# Power_Regulation.net
KiCad netlist of a schematic drawn in Altium Designer
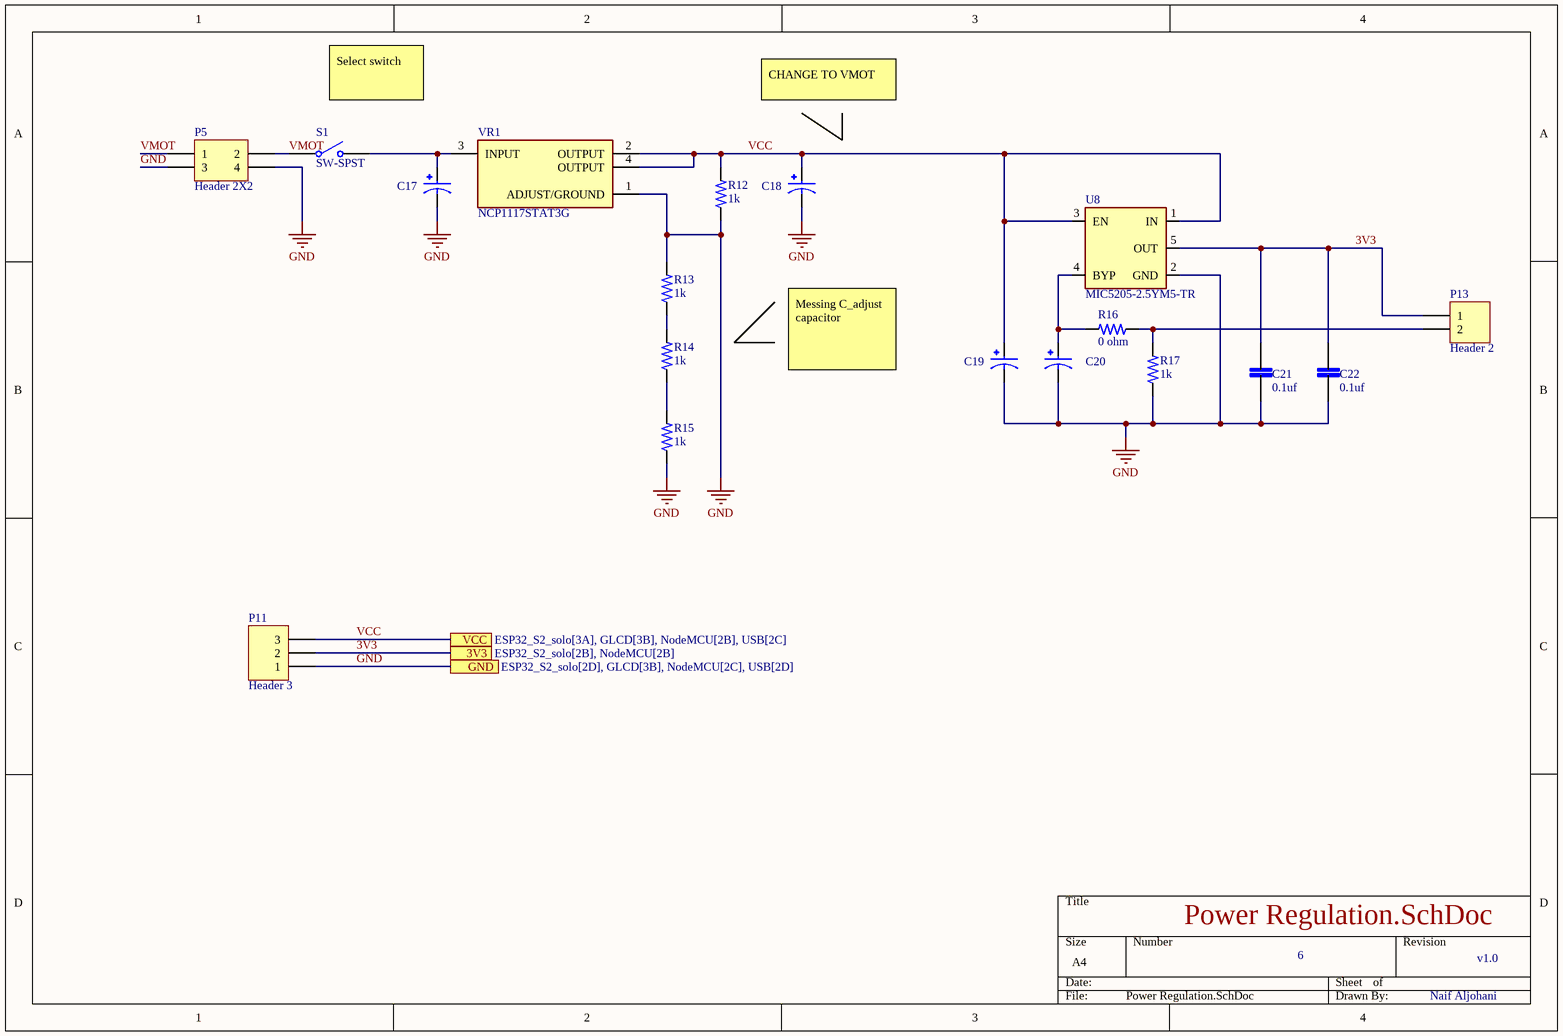
[diagram p0: Power Regulation.SchDoc]

(export (version "E")
  (design (tool "Eeschema 10.0.6"))
  (components
    (comp (ref "C17")
      (value "EEEHA1V101UP")
      (footprint "CAP_EEEHA1V101UP")
      (fields (field (name "MF") "{'manufacturer': u'Panasonic'}"))
      (libsource (lib "SnapEDA_Library") (part "EEEHA1V101UP"))
    )
    (comp (ref "C18")
      (value "EEEHA1V101UP")
      (footprint "CAP_EEEHA1V101UP")
      (fields (field (name "MF") "{'manufacturer': u'Panasonic'}"))
      (libsource (lib "SnapEDA_Library") (part "EEEHA1V101UP"))
    )
    (comp (ref "C19")
      (value "EEEHA1V101UP")
      (footprint "CAP_EEEHA1V101UP")
      (fields (field (name "MF") "{'manufacturer': u'Panasonic'}"))
      (libsource (lib "SnapEDA_Library") (part "EEEHA1V101UP"))
    )
    (comp (ref "C20")
      (value "EEEHA1V101UP")
      (footprint "CAP_EEEHA1V101UP")
      (fields (field (name "MF") "{'manufacturer': u'Panasonic'}"))
      (libsource (lib "SnapEDA_Library") (part "EEEHA1V101UP"))
    )
    (comp (ref "C21")
      (value "0.1uf")
      (footprint "CAPC2012X140N")
      (description "120PF 100V 10% 0805")
      (fields (field (name "MF") "{'manufacturer': u'AVX'}") (field (name "MP") "LD051A121KAB2A"))
      (libsource (lib "SnapEDA_Library") (part "LD051A121KAB2A"))
    )
    (comp (ref "C22")
      (value "0.1uf")
      (footprint "CAPC2012X140N")
      (description "120PF 100V 10% 0805")
      (fields (field (name "MF") "{'manufacturer': u'AVX'}") (field (name "MP") "LD051A121KAB2A"))
      (libsource (lib "SnapEDA_Library") (part "LD051A121KAB2A"))
    )
    (comp (ref "P5")
      (value "Header 2X2")
      (footprint "HDR2X2")
      (description "Header, 2-Pin, Dual row")
      (fields (field (name "PUBLISHER") "Altium Limited"))
      (libsource (lib "Miscellaneous Connectors") (part "Header 2X2"))
    )
    (comp (ref "P11")
      (value "Header 3")
      (footprint "HDR1X3")
      (description "Header, 3-Pin")
      (fields (field (name "PUBLISHER") "Altium Limited"))
      (libsource (lib "Miscellaneous Connectors") (part "Header 3"))
    )
    (comp (ref "P13")
      (value "Header 2")
      (footprint "HDR1X2")
      (description "Header, 2-Pin")
      (fields (field (name "PUBLISHER") "Altium Limited"))
      (libsource (lib "Miscellaneous Connectors") (part "Header 2"))
    )
    (comp (ref "R12")
      (value "1k")
      (footprint "RESC3115X65N")
      (description "RL73H 2B R43 1% 10 RL")
      (fields (field (name "MF") "{'manufacturer': u'TE Connectivity'}") (field (name "MP") "1-1879462-4"))
      (libsource (lib "SnapEDA_Library") (part "1-1879462-4"))
    )
    (comp (ref "R13")
      (value "1k")
      (footprint "RESC3115X65N")
      (description "RL73H 2B R43 1% 10 RL")
      (fields (field (name "MF") "{'manufacturer': u'TE Connectivity'}") (field (name "MP") "1-1879462-4"))
      (libsource (lib "SnapEDA_Library") (part "1-1879462-4"))
    )
    (comp (ref "R14")
      (value "1k")
      (footprint "RESC3115X65N")
      (description "RL73H 2B R43 1% 10 RL")
      (fields (field (name "MF") "{'manufacturer': u'TE Connectivity'}") (field (name "MP") "1-1879462-4"))
      (libsource (lib "SnapEDA_Library") (part "1-1879462-4"))
    )
    (comp (ref "R15")
      (value "1k")
      (footprint "RESC3115X65N")
      (description "RL73H 2B R43 1% 10 RL")
      (fields (field (name "MF") "{'manufacturer': u'TE Connectivity'}") (field (name "MP") "1-1879462-4"))
      (libsource (lib "SnapEDA_Library") (part "1-1879462-4"))
    )
    (comp (ref "R16")
      (value "0 ohm")
      (footprint "RESC3115X65N")
      (description "RL73H 2B R43 1% 10 RL")
      (fields (field (name "MF") "{'manufacturer': u'TE Connectivity'}") (field (name "MP") "1-1879462-4"))
      (libsource (lib "SnapEDA_Library") (part "1-1879462-4"))
    )
    (comp (ref "R17")
      (value "1k")
      (footprint "RESC3115X65N")
      (description "RL73H 2B R43 1% 10 RL")
      (fields (field (name "MF") "{'manufacturer': u'TE Connectivity'}") (field (name "MP") "1-1879462-4"))
      (libsource (lib "SnapEDA_Library") (part "1-1879462-4"))
    )
    (comp (ref "S1")
      (value "SW-SPST")
      (footprint "SPST-2")
      (description "Single-Pole, Single-Throw Switch")
      (fields (field (name "PUBLISHER") "Altium Limited"))
      (libsource (lib "Miscellaneous Devices") (part "SW-SPST"))
    )
    (comp (ref "U8")
      (value "MIC5205-2.5YM5-TR")
      (footprint "SOT95P280X145-5N")
      (description "MIC5205 Series 3 V Fixed Output 150 mA SMT Low-Noise LDO Regulator - SOT-23-5")
      (fields (field (name "MF") "{'manufacturer': u'Microchip Technology'}"))
      (libsource (lib "SnapEDA_Library") (part "MIC5205-2.5YM5-TR"))
    )
    (comp (ref "VR1")
      (value "NCP1117STAT3G")
      (footprint "VREG_NCP1117STAT3G")
      (description "Linear Voltage Regulator IC 1 Output 1A SOT-223")
      (fields (field (name "MF") "{'manufacturer': u'ON Semiconductor'}"))
      (libsource (lib "SnapEDA_Library") (part "NCP1117STAT3G"))
    )
  )
  (nets
    (net (code "1") (name "/3V3") (class "Default")
      (node (ref "C21") (pin "2") (pinfunction "2_2") (pintype "passive"))
      (node (ref "C22") (pin "2") (pinfunction "2_2") (pintype "passive"))
      (node (ref "P11") (pin "2") (pinfunction "2_2") (pintype "passive"))
      (node (ref "P13") (pin "1") (pinfunction "1_1") (pintype "passive"))
      (node (ref "U8") (pin "5") (pinfunction "OUT_5") (pintype "passive"))
    )
    (net (code "2") (name "/VCC") (class "Default")
      (node (ref "C18") (pin "1") (pinfunction "1_1") (pintype "passive"))
      (node (ref "C19") (pin "1") (pinfunction "1_1") (pintype "passive"))
      (node (ref "P11") (pin "3") (pinfunction "3_3") (pintype "passive"))
      (node (ref "R12") (pin "2") (pinfunction "2_2") (pintype "passive"))
      (node (ref "U8") (pin "1") (pinfunction "IN_1") (pintype "passive"))
      (node (ref "U8") (pin "3") (pinfunction "EN_3") (pintype "passive"))
      (node (ref "VR1") (pin "2") (pinfunction "OUTPUT_2") (pintype "passive"))
      (node (ref "VR1") (pin "4") (pinfunction "OUTPUT_4") (pintype "passive"))
    )
    (net (code "3") (name "/VMOT") (class "Default")
      (node (ref "P5") (pin "1") (pinfunction "1_1") (pintype "passive"))
      (node (ref "P5") (pin "2") (pinfunction "2_2") (pintype "passive"))
      (node (ref "S1") (pin "1") (pinfunction "COMMON_1") (pintype "passive"))
    )
    (net (code "4") (name "GND") (class "Default")
      (node (ref "C17") (pin "2") (pinfunction "2_2") (pintype "power_in"))
      (node (ref "C18") (pin "2") (pinfunction "2_2") (pintype "power_in"))
      (node (ref "C19") (pin "2") (pinfunction "2_2") (pintype "power_in"))
      (node (ref "C20") (pin "2") (pinfunction "2_2") (pintype "power_in"))
      (node (ref "C21") (pin "1") (pinfunction "1_1") (pintype "passive"))
      (node (ref "C22") (pin "1") (pinfunction "1_1") (pintype "passive"))
      (node (ref "P11") (pin "1") (pinfunction "1_1") (pintype "passive"))
      (node (ref "P5") (pin "3") (pinfunction "3_3") (pintype "passive"))
      (node (ref "P5") (pin "4") (pinfunction "4_4") (pintype "passive"))
      (node (ref "R12") (pin "1") (pinfunction "1_1") (pintype "passive"))
      (node (ref "R13") (pin "2") (pinfunction "2_2") (pintype "passive"))
      (node (ref "R15") (pin "1") (pinfunction "1_1") (pintype "passive"))
      (node (ref "R17") (pin "1") (pinfunction "1_1") (pintype "passive"))
      (node (ref "U8") (pin "2") (pinfunction "GND_2") (pintype "power_in"))
      (node (ref "VR1") (pin "1") (pinfunction "ADJUST/GROUND_1") (pintype "passive"))
    )
    (net (code "5") (name "Net-(P13-Pad2)") (class "Default")
      (node (ref "P13") (pin "2") (pinfunction "2_2") (pintype "passive"))
      (node (ref "R16") (pin "1") (pinfunction "1_1") (pintype "passive"))
      (node (ref "R17") (pin "2") (pinfunction "2_2") (pintype "passive"))
    )
    (net (code "6") (name "Net-(R13-Pad1)") (class "Default")
      (node (ref "R13") (pin "1") (pinfunction "1_1") (pintype "passive"))
      (node (ref "R14") (pin "2") (pinfunction "2_2") (pintype "passive"))
    )
    (net (code "7") (name "Net-(R14-Pad1)") (class "Default")
      (node (ref "R14") (pin "1") (pinfunction "1_1") (pintype "passive"))
      (node (ref "R15") (pin "2") (pinfunction "2_2") (pintype "passive"))
    )
    (net (code "8") (name "Net-(S1-NO)") (class "Default")
      (node (ref "C17") (pin "1") (pinfunction "1_1") (pintype "passive"))
      (node (ref "S1") (pin "2") (pinfunction "NO_2") (pintype "passive"))
      (node (ref "VR1") (pin "3") (pinfunction "INPUT_3") (pintype "passive"))
    )
    (net (code "9") (name "Net-(U8-BYP)") (class "Default")
      (node (ref "C20") (pin "1") (pinfunction "1_1") (pintype "passive"))
      (node (ref "R16") (pin "2") (pinfunction "2_2") (pintype "passive"))
      (node (ref "U8") (pin "4") (pinfunction "BYP_4") (pintype "passive"))
    )
  )
)
